# S03.net
KiCad netlist of a schematic drawn in Altium Designer
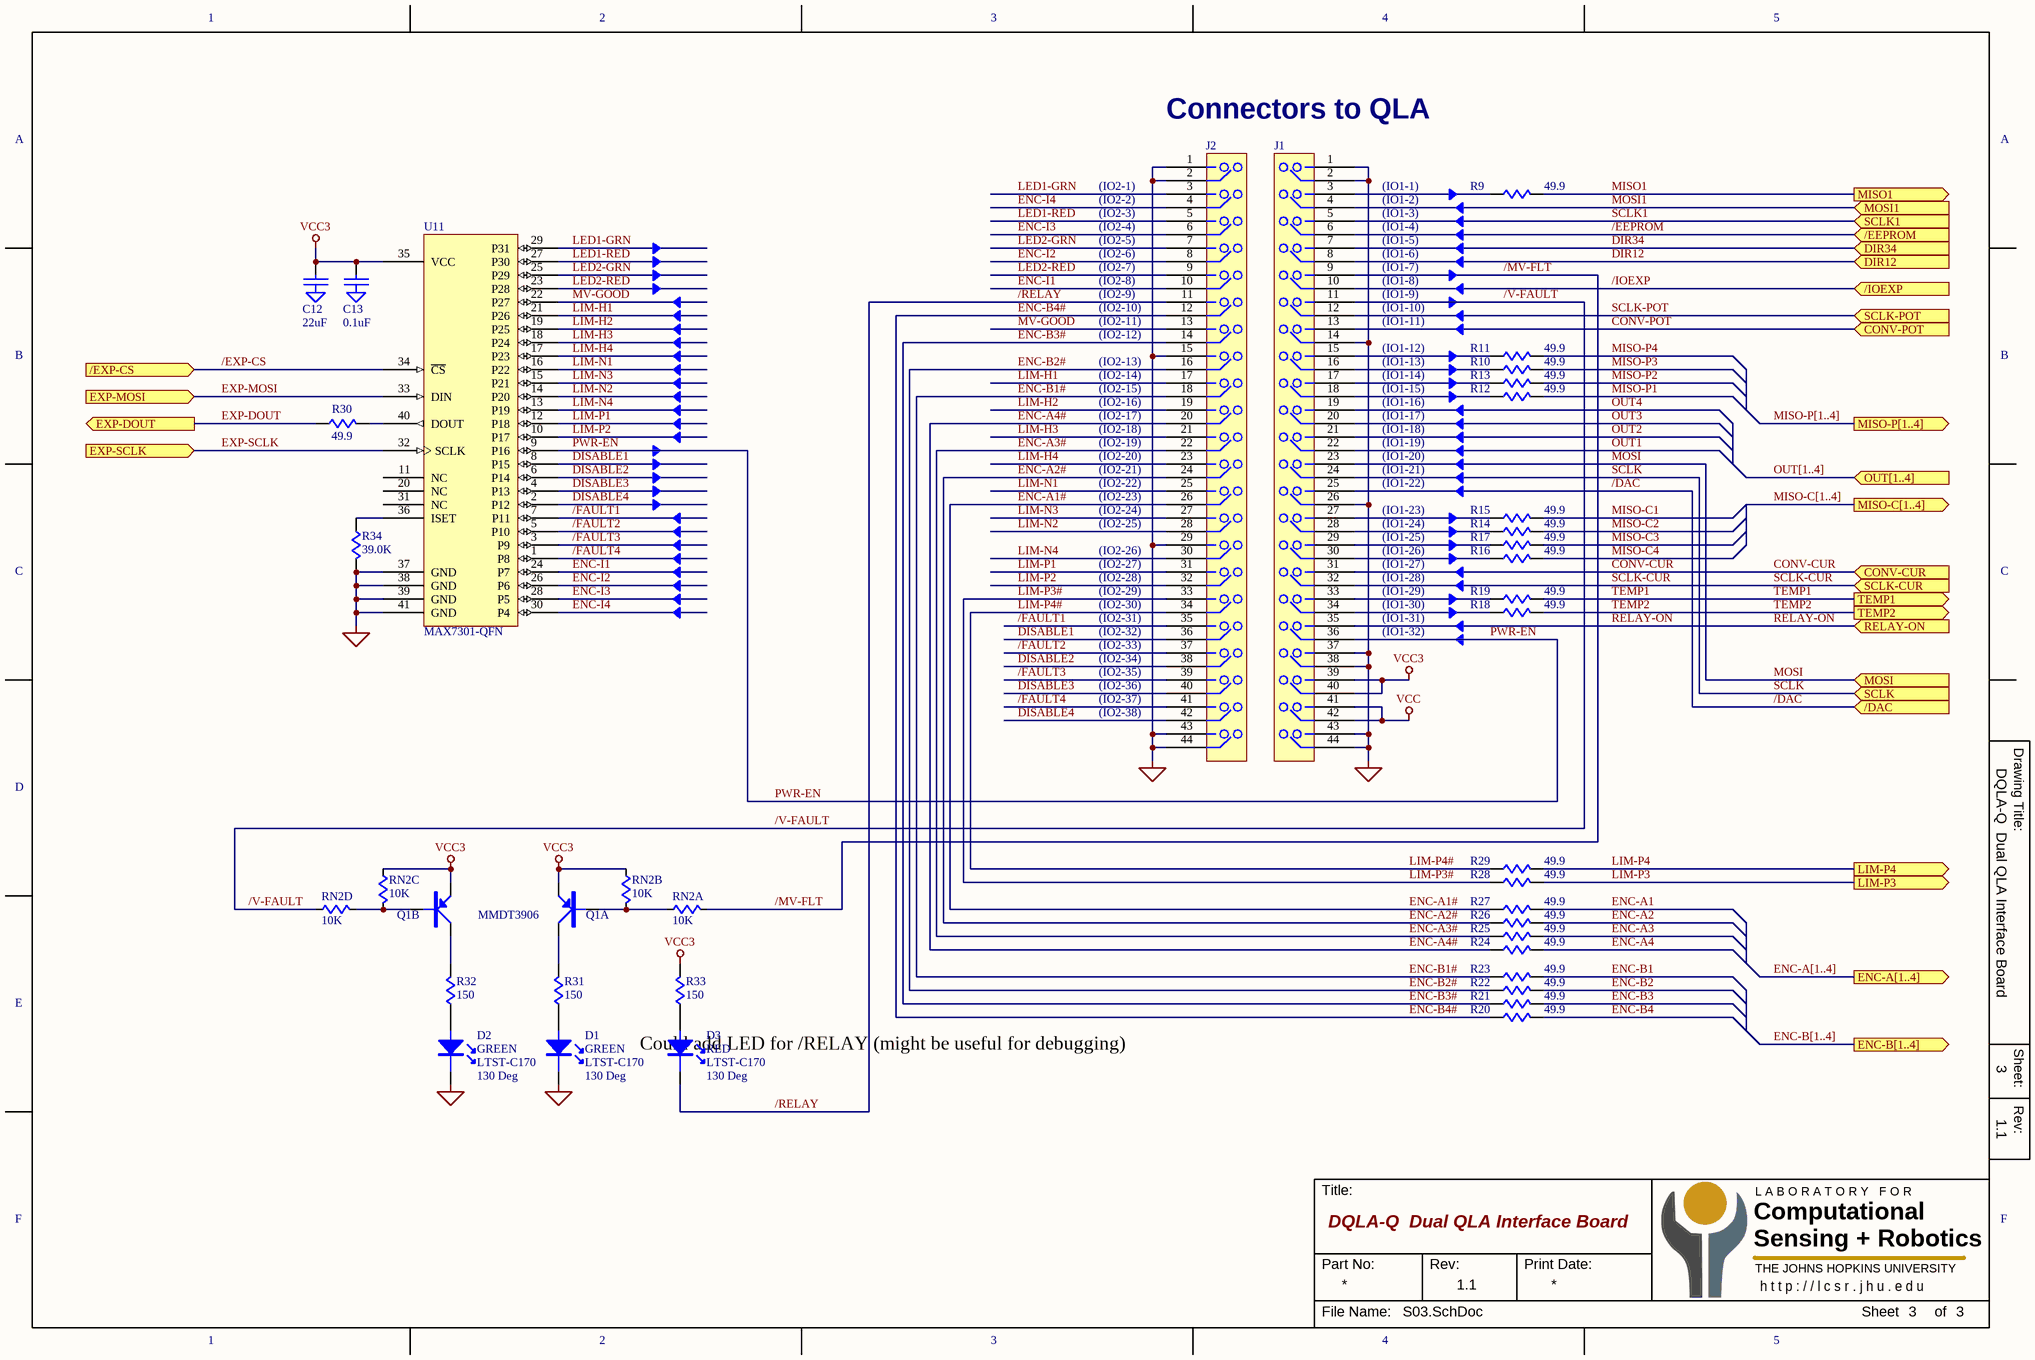
[diagram p0: S03.SchDoc]

(export (version "E")
  (design (tool "Eeschema 10.0.6"))
  (components
    (comp (ref "C12") (value "22uF") (footprint "C0805") (libsource (lib "LibJHU") (part "CAP-GND")))
    (comp (ref "C13") (value "0.1uF") (footprint "C0402") (libsource (lib "LibJHU") (part "CAP-GND")))
    (comp (ref "D1")
      (value "LED")
      (footprint "LED-0805")
      (fields
        (field (name "COLOR") "GREEN")
        (field (name "P/N") "LTST-C170")
        (field (name "ANGLE") "130 Deg")
      )
      (libsource (lib "LibJHU") (part "LED"))
    )
    (comp (ref "D2")
      (value "LED")
      (footprint "LED-0805")
      (fields
        (field (name "COLOR") "GREEN")
        (field (name "P/N") "LTST-C170")
        (field (name "ANGLE") "130 Deg")
      )
      (libsource (lib "LibJHU") (part "LED"))
    )
    (comp (ref "D3")
      (value "LED")
      (footprint "LED-0805")
      (fields (field (name "COLOR") "RED") (field (name "P/N") "LTST-C170") (field (name "ANGLE") "130 Deg"))
      (libsource (lib "LibJHU") (part "LED"))
    )
    (comp (ref "J1")
      (value "HEADER 22x2-1")
      (footprint "HDR-22x2-2MM")
      (libsource (lib "LibJHU") (part "HEADER 22x2-1"))
    )
    (comp (ref "J2")
      (value "HEADER 22x2-1")
      (footprint "HDR-22x2-2MM")
      (libsource (lib "LibJHU") (part "HEADER 22x2-1"))
    )
    (comp (ref "Q1")
      (value "MMDT3906")
      (footprint "SC70-6-NP")
      (libsource (lib "LibJHU") (part "PNP-DUAL-DIAG"))
    )
    (comp (ref "R9") (value "49.9") (footprint "R0402") (libsource (lib "LibJHU") (part "R")))
    (comp (ref "R10") (value "49.9") (footprint "R0402") (libsource (lib "LibJHU") (part "R")))
    (comp (ref "R11") (value "49.9") (footprint "R0402") (libsource (lib "LibJHU") (part "R")))
    (comp (ref "R12") (value "49.9") (footprint "R0402") (libsource (lib "LibJHU") (part "R")))
    (comp (ref "R13") (value "49.9") (footprint "R0402") (libsource (lib "LibJHU") (part "R")))
    (comp (ref "R14") (value "49.9") (footprint "R0402") (libsource (lib "LibJHU") (part "R")))
    (comp (ref "R15") (value "49.9") (footprint "R0402") (libsource (lib "LibJHU") (part "R")))
    (comp (ref "R16") (value "49.9") (footprint "R0402") (libsource (lib "LibJHU") (part "R")))
    (comp (ref "R17") (value "49.9") (footprint "R0402") (libsource (lib "LibJHU") (part "R")))
    (comp (ref "R18") (value "49.9") (footprint "R0402") (libsource (lib "LibJHU") (part "R")))
    (comp (ref "R19") (value "49.9") (footprint "R0402") (libsource (lib "LibJHU") (part "R")))
    (comp (ref "R20") (value "49.9") (footprint "R0402") (libsource (lib "LibJHU") (part "R")))
    (comp (ref "R21") (value "49.9") (footprint "R0402") (libsource (lib "LibJHU") (part "R")))
    (comp (ref "R22") (value "49.9") (footprint "R0402") (libsource (lib "LibJHU") (part "R")))
    (comp (ref "R23") (value "49.9") (footprint "R0402") (libsource (lib "LibJHU") (part "R")))
    (comp (ref "R24") (value "49.9") (footprint "R0402") (libsource (lib "LibJHU") (part "R")))
    (comp (ref "R25") (value "49.9") (footprint "R0402") (libsource (lib "LibJHU") (part "R")))
    (comp (ref "R26") (value "49.9") (footprint "R0402") (libsource (lib "LibJHU") (part "R")))
    (comp (ref "R27") (value "49.9") (footprint "R0402") (libsource (lib "LibJHU") (part "R")))
    (comp (ref "R28") (value "49.9") (footprint "R0402") (libsource (lib "LibJHU") (part "R")))
    (comp (ref "R29") (value "49.9") (footprint "R0402") (libsource (lib "LibJHU") (part "R")))
    (comp (ref "R30") (value "49.9") (footprint "R0402") (libsource (lib "LibJHU") (part "R")))
    (comp (ref "R31") (value "150") (footprint "R0603") (libsource (lib "LibJHU") (part "R")))
    (comp (ref "R32") (value "150") (footprint "R0603") (libsource (lib "LibJHU") (part "R")))
    (comp (ref "R33") (value "150") (footprint "R0603") (libsource (lib "LibJHU") (part "R")))
    (comp (ref "R34") (value "39.0K") (footprint "R0402") (libsource (lib "") (part "R_1")))
    (comp (ref "RN2")
      (value "10K")
      (footprint "RN-742C083")
      (libsource (lib "LibJHU") (part "RN-DISC-SM-4X"))
    )
    (comp (ref "U11")
      (value "MAX7301-QFN")
      (footprint "QFN-40-6mm")
      (libsource (lib "LibJHU") (part "MAX7301-QFN"))
    )
  )
  (nets
    (net (code "1") (name "/CONV-CUR") (class "Default")
      (node (ref "J1") (pin "31") (pinfunction "31_31") (pintype "passive"))
    )
    (net (code "2") (name "/CONV-POT") (class "Default")
      (node (ref "J1") (pin "13") (pinfunction "13_13") (pintype "passive"))
    )
    (net (code "3") (name "/DIR12") (class "Default")
      (node (ref "J1") (pin "8") (pinfunction "8_8") (pintype "passive"))
    )
    (net (code "4") (name "/DIR34") (class "Default")
      (node (ref "J1") (pin "7") (pinfunction "7_7") (pintype "passive"))
    )
    (net (code "5") (name "/DISABLE1") (class "Default")
      (node (ref "J2") (pin "36") (pinfunction "36_36") (pintype "passive"))
      (node (ref "U11") (pin "8") (pinfunction "P15_8") (pintype "bidirectional"))
    )
    (net (code "6") (name "/DISABLE2") (class "Default")
      (node (ref "J2") (pin "38") (pinfunction "38_38") (pintype "passive"))
      (node (ref "U11") (pin "6") (pinfunction "P14_6") (pintype "bidirectional"))
    )
    (net (code "7") (name "/DISABLE3") (class "Default")
      (node (ref "J2") (pin "40") (pinfunction "40_40") (pintype "passive"))
      (node (ref "U11") (pin "4") (pinfunction "P13_4") (pintype "bidirectional"))
    )
    (net (code "8") (name "/DISABLE4") (class "Default")
      (node (ref "J2") (pin "42") (pinfunction "42_42") (pintype "passive"))
      (node (ref "U11") (pin "2") (pinfunction "P12_2") (pintype "bidirectional"))
    )
    (net (code "9") (name "/ENC-A1") (class "Default")
      (node (ref "R27") (pin "2") (pinfunction "2_2") (pintype "passive"))
    )
    (net (code "10") (name "/ENC-A1#") (class "Default")
      (node (ref "J2") (pin "26") (pinfunction "26_26") (pintype "passive"))
      (node (ref "R27") (pin "1") (pinfunction "1_1") (pintype "passive"))
    )
    (net (code "11") (name "/ENC-A2") (class "Default")
      (node (ref "R26") (pin "2") (pinfunction "2_2") (pintype "passive"))
    )
    (net (code "12") (name "/ENC-A2#") (class "Default")
      (node (ref "J2") (pin "24") (pinfunction "24_24") (pintype "passive"))
      (node (ref "R26") (pin "1") (pinfunction "1_1") (pintype "passive"))
    )
    (net (code "13") (name "/ENC-A3") (class "Default")
      (node (ref "R25") (pin "2") (pinfunction "2_2") (pintype "passive"))
    )
    (net (code "14") (name "/ENC-A3#") (class "Default")
      (node (ref "J2") (pin "22") (pinfunction "22_22") (pintype "passive"))
      (node (ref "R25") (pin "1") (pinfunction "1_1") (pintype "passive"))
    )
    (net (code "15") (name "/ENC-A4") (class "Default")
      (node (ref "R24") (pin "2") (pinfunction "2_2") (pintype "passive"))
    )
    (net (code "16") (name "/ENC-A4#") (class "Default")
      (node (ref "J2") (pin "20") (pinfunction "20_20") (pintype "passive"))
      (node (ref "R24") (pin "1") (pinfunction "1_1") (pintype "passive"))
    )
    (net (code "18") (name "/ENC-B1") (class "Default")
      (node (ref "R23") (pin "2") (pinfunction "2_2") (pintype "passive"))
    )
    (net (code "19") (name "/ENC-B1#") (class "Default")
      (node (ref "J2") (pin "18") (pinfunction "18_18") (pintype "passive"))
      (node (ref "R23") (pin "1") (pinfunction "1_1") (pintype "passive"))
    )
    (net (code "20") (name "/ENC-B2") (class "Default")
      (node (ref "R22") (pin "2") (pinfunction "2_2") (pintype "passive"))
    )
    (net (code "21") (name "/ENC-B2#") (class "Default")
      (node (ref "J2") (pin "16") (pinfunction "16_16") (pintype "passive"))
      (node (ref "R22") (pin "1") (pinfunction "1_1") (pintype "passive"))
    )
    (net (code "22") (name "/ENC-B3") (class "Default")
      (node (ref "R21") (pin "2") (pinfunction "2_2") (pintype "passive"))
    )
    (net (code "23") (name "/ENC-B3#") (class "Default")
      (node (ref "J2") (pin "14") (pinfunction "14_14") (pintype "passive"))
      (node (ref "R21") (pin "1") (pinfunction "1_1") (pintype "passive"))
    )
    (net (code "24") (name "/ENC-B4") (class "Default")
      (node (ref "R20") (pin "2") (pinfunction "2_2") (pintype "passive"))
    )
    (net (code "25") (name "/ENC-B4#") (class "Default")
      (node (ref "J2") (pin "12") (pinfunction "12_12") (pintype "passive"))
      (node (ref "R20") (pin "1") (pinfunction "1_1") (pintype "passive"))
    )
    (net (code "27") (name "/ENC-I1") (class "Default")
      (node (ref "J2") (pin "10") (pinfunction "10_10") (pintype "passive"))
      (node (ref "U11") (pin "24") (pinfunction "P7_24") (pintype "bidirectional"))
    )
    (net (code "28") (name "/ENC-I2") (class "Default")
      (node (ref "J2") (pin "8") (pinfunction "8_8") (pintype "passive"))
      (node (ref "U11") (pin "26") (pinfunction "P6_26") (pintype "bidirectional"))
    )
    (net (code "29") (name "/ENC-I3") (class "Default")
      (node (ref "J2") (pin "6") (pinfunction "6_6") (pintype "passive"))
      (node (ref "U11") (pin "28") (pinfunction "P5_28") (pintype "bidirectional"))
    )
    (net (code "30") (name "/ENC-I4") (class "Default")
      (node (ref "J2") (pin "4") (pinfunction "4_4") (pintype "passive"))
      (node (ref "U11") (pin "30") (pinfunction "P4_30") (pintype "bidirectional"))
    )
    (net (code "31") (name "/EXP-DOUT") (class "Default")
      (node (ref "R30") (pin "1") (pinfunction "1_1") (pintype "passive"))
    )
    (net (code "32") (name "/EXP-MOSI") (class "Default")
      (node (ref "U11") (pin "33") (pinfunction "DIN_33") (pintype "input"))
    )
    (net (code "33") (name "/EXP-SCLK") (class "Default")
      (node (ref "U11") (pin "32") (pinfunction "SCLK_32") (pintype "input"))
    )
    (net (code "34") (name "/LED1-GRN") (class "Default")
      (node (ref "J2") (pin "3") (pinfunction "3_3") (pintype "passive"))
      (node (ref "U11") (pin "29") (pinfunction "P31_29") (pintype "bidirectional"))
    )
    (net (code "35") (name "/LED1-RED") (class "Default")
      (node (ref "J2") (pin "5") (pinfunction "5_5") (pintype "passive"))
      (node (ref "U11") (pin "27") (pinfunction "P30_27") (pintype "bidirectional"))
    )
    (net (code "36") (name "/LED2-GRN") (class "Default")
      (node (ref "J2") (pin "7") (pinfunction "7_7") (pintype "passive"))
      (node (ref "U11") (pin "25") (pinfunction "P29_25") (pintype "bidirectional"))
    )
    (net (code "37") (name "/LED2-RED") (class "Default")
      (node (ref "J2") (pin "9") (pinfunction "9_9") (pintype "passive"))
      (node (ref "U11") (pin "23") (pinfunction "P28_23") (pintype "bidirectional"))
    )
    (net (code "38") (name "/LIM-H1") (class "Default")
      (node (ref "J2") (pin "17") (pinfunction "17_17") (pintype "passive"))
      (node (ref "U11") (pin "21") (pinfunction "P26_21") (pintype "bidirectional"))
    )
    (net (code "39") (name "/LIM-H2") (class "Default")
      (node (ref "J2") (pin "19") (pinfunction "19_19") (pintype "passive"))
      (node (ref "U11") (pin "19") (pinfunction "P25_19") (pintype "bidirectional"))
    )
    (net (code "40") (name "/LIM-H3") (class "Default")
      (node (ref "J2") (pin "21") (pinfunction "21_21") (pintype "passive"))
      (node (ref "U11") (pin "18") (pinfunction "P24_18") (pintype "bidirectional"))
    )
    (net (code "41") (name "/LIM-H4") (class "Default")
      (node (ref "J2") (pin "23") (pinfunction "23_23") (pintype "passive"))
      (node (ref "U11") (pin "17") (pinfunction "P23_17") (pintype "bidirectional"))
    )
    (net (code "42") (name "/LIM-N1") (class "Default")
      (node (ref "J2") (pin "25") (pinfunction "25_25") (pintype "passive"))
      (node (ref "U11") (pin "16") (pinfunction "P22_16") (pintype "bidirectional"))
    )
    (net (code "43") (name "/LIM-N2") (class "Default")
      (node (ref "J2") (pin "28") (pinfunction "28_28") (pintype "passive"))
      (node (ref "U11") (pin "14") (pinfunction "P20_14") (pintype "bidirectional"))
    )
    (net (code "44") (name "/LIM-N3") (class "Default")
      (node (ref "J2") (pin "27") (pinfunction "27_27") (pintype "passive"))
      (node (ref "U11") (pin "15") (pinfunction "P21_15") (pintype "bidirectional"))
    )
    (net (code "45") (name "/LIM-N4") (class "Default")
      (node (ref "J2") (pin "30") (pinfunction "30_30") (pintype "passive"))
      (node (ref "U11") (pin "13") (pinfunction "P19_13") (pintype "bidirectional"))
    )
    (net (code "46") (name "/LIM-P1") (class "Default")
      (node (ref "J2") (pin "31") (pinfunction "31_31") (pintype "passive"))
      (node (ref "U11") (pin "12") (pinfunction "P18_12") (pintype "bidirectional"))
    )
    (net (code "47") (name "/LIM-P2") (class "Default")
      (node (ref "J2") (pin "32") (pinfunction "32_32") (pintype "passive"))
      (node (ref "U11") (pin "10") (pinfunction "P17_10") (pintype "bidirectional"))
    )
    (net (code "48") (name "/LIM-P3") (class "Default")
      (node (ref "R28") (pin "2") (pinfunction "2_2") (pintype "passive"))
    )
    (net (code "49") (name "/LIM-P3#") (class "Default")
      (node (ref "J2") (pin "33") (pinfunction "33_33") (pintype "passive"))
      (node (ref "R28") (pin "1") (pinfunction "1_1") (pintype "passive"))
    )
    (net (code "50") (name "/LIM-P4") (class "Default")
      (node (ref "R29") (pin "2") (pinfunction "2_2") (pintype "passive"))
    )
    (net (code "51") (name "/LIM-P4#") (class "Default")
      (node (ref "J2") (pin "34") (pinfunction "34_34") (pintype "passive"))
      (node (ref "R29") (pin "1") (pinfunction "1_1") (pintype "passive"))
    )
    (net (code "52") (name "/MISO-C1") (class "Default")
      (node (ref "R15") (pin "2") (pinfunction "2_2") (pintype "passive"))
    )
    (net (code "53") (name "/MISO-C2") (class "Default")
      (node (ref "R14") (pin "2") (pinfunction "2_2") (pintype "passive"))
    )
    (net (code "54") (name "/MISO-C3") (class "Default")
      (node (ref "R17") (pin "2") (pinfunction "2_2") (pintype "passive"))
    )
    (net (code "55") (name "/MISO-C4") (class "Default")
      (node (ref "R16") (pin "2") (pinfunction "2_2") (pintype "passive"))
    )
    (net (code "57") (name "/MISO-P1") (class "Default")
      (node (ref "R12") (pin "2") (pinfunction "2_2") (pintype "passive"))
    )
    (net (code "58") (name "/MISO-P2") (class "Default")
      (node (ref "R13") (pin "2") (pinfunction "2_2") (pintype "passive"))
    )
    (net (code "59") (name "/MISO-P3") (class "Default")
      (node (ref "R10") (pin "2") (pinfunction "2_2") (pintype "passive"))
    )
    (net (code "60") (name "/MISO-P4") (class "Default")
      (node (ref "R11") (pin "2") (pinfunction "2_2") (pintype "passive"))
    )
    (net (code "62") (name "/MISO1") (class "Default")
      (node (ref "R9") (pin "2") (pinfunction "2_2") (pintype "passive"))
    )
    (net (code "63") (name "/MOSI") (class "Default")
      (node (ref "J1") (pin "23") (pinfunction "23_23") (pintype "passive"))
    )
    (net (code "64") (name "/MOSI1") (class "Default")
      (node (ref "J1") (pin "4") (pinfunction "4_4") (pintype "passive"))
    )
    (net (code "65") (name "/MV-GOOD") (class "Default")
      (node (ref "J2") (pin "13") (pinfunction "13_13") (pintype "passive"))
      (node (ref "U11") (pin "22") (pinfunction "P27_22") (pintype "bidirectional"))
    )
    (net (code "66") (name "/OUT1") (class "Default")
      (node (ref "J1") (pin "22") (pinfunction "22_22") (pintype "passive"))
    )
    (net (code "67") (name "/OUT2") (class "Default")
      (node (ref "J1") (pin "21") (pinfunction "21_21") (pintype "passive"))
    )
    (net (code "68") (name "/OUT3") (class "Default")
      (node (ref "J1") (pin "20") (pinfunction "20_20") (pintype "passive"))
    )
    (net (code "69") (name "/OUT4") (class "Default")
      (node (ref "J1") (pin "19") (pinfunction "19_19") (pintype "passive"))
    )
    (net (code "71") (name "/PWR-EN") (class "Default")
      (node (ref "J1") (pin "36") (pinfunction "36_36") (pintype "passive"))
      (node (ref "U11") (pin "9") (pinfunction "P16_9") (pintype "bidirectional"))
    )
    (net (code "72") (name "/RELAY-ON") (class "Default")
      (node (ref "J1") (pin "35") (pinfunction "35_35") (pintype "passive"))
    )
    (net (code "73") (name "/SCLK") (class "Default")
      (node (ref "J1") (pin "24") (pinfunction "24_24") (pintype "passive"))
    )
    (net (code "74") (name "/SCLK-CUR") (class "Default")
      (node (ref "J1") (pin "32") (pinfunction "32_32") (pintype "passive"))
    )
    (net (code "75") (name "/SCLK-POT") (class "Default")
      (node (ref "J1") (pin "12") (pinfunction "12_12") (pintype "passive"))
    )
    (net (code "76") (name "/SCLK1") (class "Default")
      (node (ref "J1") (pin "5") (pinfunction "5_5") (pintype "passive"))
    )
    (net (code "77") (name "/TEMP1") (class "Default")
      (node (ref "R19") (pin "2") (pinfunction "2_2") (pintype "passive"))
    )
    (net (code "78") (name "/TEMP2") (class "Default")
      (node (ref "R18") (pin "2") (pinfunction "2_2") (pintype "passive"))
    )
    (net (code "79") (name "/{slash}DAC") (class "Default")
      (node (ref "J1") (pin "25") (pinfunction "25_25") (pintype "passive"))
    )
    (net (code "80") (name "/{slash}EEPROM") (class "Default")
      (node (ref "J1") (pin "6") (pinfunction "6_6") (pintype "passive"))
    )
    (net (code "81") (name "/{slash}EXP-CS") (class "Default")
      (node (ref "U11") (pin "34") (pinfunction "CS_34") (pintype "input"))
    )
    (net (code "82") (name "/{slash}FAULT1") (class "Default")
      (node (ref "J2") (pin "35") (pinfunction "35_35") (pintype "passive"))
      (node (ref "U11") (pin "7") (pinfunction "P11_7") (pintype "bidirectional"))
    )
    (net (code "83") (name "/{slash}FAULT2") (class "Default")
      (node (ref "J2") (pin "37") (pinfunction "37_37") (pintype "passive"))
      (node (ref "U11") (pin "5") (pinfunction "P10_5") (pintype "bidirectional"))
    )
    (net (code "84") (name "/{slash}FAULT3") (class "Default")
      (node (ref "J2") (pin "39") (pinfunction "39_39") (pintype "passive"))
      (node (ref "U11") (pin "3") (pinfunction "P9_3") (pintype "bidirectional"))
    )
    (net (code "85") (name "/{slash}FAULT4") (class "Default")
      (node (ref "J2") (pin "41") (pinfunction "41_41") (pintype "passive"))
      (node (ref "U11") (pin "1") (pinfunction "P8_1") (pintype "bidirectional"))
    )
    (net (code "86") (name "/{slash}IOEXP") (class "Default")
      (node (ref "J1") (pin "10") (pinfunction "10_10") (pintype "passive"))
    )
    (net (code "87") (name "/{slash}MV-FLT") (class "Default")
      (node (ref "J1") (pin "9") (pinfunction "9_9") (pintype "passive"))
      (node (ref "RN2") (pin "1") (pinfunction "1_1") (pintype "passive"))
    )
    (net (code "88") (name "/{slash}RELAY") (class "Default")
      (node (ref "D3") (pin "1") (pinfunction "C_1") (pintype "passive"))
      (node (ref "J2") (pin "11") (pinfunction "11_11") (pintype "passive"))
    )
    (net (code "89") (name "/{slash}V-FAULT") (class "Default")
      (node (ref "J1") (pin "11") (pinfunction "11_11") (pintype "passive"))
      (node (ref "RN2") (pin "4") (pinfunction "4_4") (pintype "passive"))
    )
    (net (code "90") (name "GND") (class "Default")
      (node (ref "C12") (pin "2") (pinfunction "GND_2") (pintype "power_in"))
      (node (ref "C13") (pin "2") (pinfunction "GND_2") (pintype "power_in"))
      (node (ref "D1") (pin "1") (pinfunction "C_1") (pintype "passive"))
      (node (ref "D2") (pin "1") (pinfunction "C_1") (pintype "passive"))
      (node (ref "J1") (pin "1") (pinfunction "1_1") (pintype "passive"))
      (node (ref "J1") (pin "14") (pinfunction "14_14") (pintype "passive"))
      (node (ref "J1") (pin "2") (pinfunction "2_2") (pintype "passive"))
      (node (ref "J1") (pin "26") (pinfunction "26_26") (pintype "passive"))
      (node (ref "J1") (pin "37") (pinfunction "37_37") (pintype "passive"))
      (node (ref "J1") (pin "38") (pinfunction "38_38") (pintype "passive"))
      (node (ref "J1") (pin "43") (pinfunction "43_43") (pintype "passive"))
      (node (ref "J1") (pin "44") (pinfunction "44_44") (pintype "passive"))
      (node (ref "J2") (pin "1") (pinfunction "1_1") (pintype "passive"))
      (node (ref "J2") (pin "15") (pinfunction "15_15") (pintype "passive"))
      (node (ref "J2") (pin "2") (pinfunction "2_2") (pintype "passive"))
      (node (ref "J2") (pin "29") (pinfunction "29_29") (pintype "passive"))
      (node (ref "J2") (pin "43") (pinfunction "43_43") (pintype "passive"))
      (node (ref "J2") (pin "44") (pinfunction "44_44") (pintype "passive"))
      (node (ref "R34") (pin "2") (pinfunction "2_2") (pintype "passive"))
      (node (ref "U11") (pin "37") (pinfunction "GND_37") (pintype "power_in"))
      (node (ref "U11") (pin "38") (pinfunction "GND_38") (pintype "power_in"))
      (node (ref "U11") (pin "39") (pinfunction "GND_39") (pintype "power_in"))
      (node (ref "U11") (pin "41") (pinfunction "GND_41") (pintype "power_in"))
    )
    (net (code "91") (name "Net-(D1-A)") (class "Default")
      (node (ref "D1") (pin "2") (pinfunction "A_2") (pintype "passive"))
      (node (ref "R31") (pin "1") (pinfunction "1_1") (pintype "passive"))
    )
    (net (code "92") (name "Net-(D2-A)") (class "Default")
      (node (ref "D2") (pin "2") (pinfunction "A_2") (pintype "passive"))
      (node (ref "R32") (pin "1") (pinfunction "1_1") (pintype "passive"))
    )
    (net (code "93") (name "Net-(D3-A)") (class "Default")
      (node (ref "D3") (pin "2") (pinfunction "A_2") (pintype "passive"))
      (node (ref "R33") (pin "1") (pinfunction "1_1") (pintype "passive"))
    )
    (net (code "94") (name "Net-(J1-Pad3)") (class "Default")
      (node (ref "J1") (pin "3") (pinfunction "3_3") (pintype "passive"))
      (node (ref "R9") (pin "1") (pinfunction "1_1") (pintype "passive"))
    )
    (net (code "95") (name "Net-(J1-Pad15)") (class "Default")
      (node (ref "J1") (pin "15") (pinfunction "15_15") (pintype "passive"))
      (node (ref "R11") (pin "1") (pinfunction "1_1") (pintype "passive"))
    )
    (net (code "96") (name "Net-(J1-Pad16)") (class "Default")
      (node (ref "J1") (pin "16") (pinfunction "16_16") (pintype "passive"))
      (node (ref "R10") (pin "1") (pinfunction "1_1") (pintype "passive"))
    )
    (net (code "97") (name "Net-(J1-Pad17)") (class "Default")
      (node (ref "J1") (pin "17") (pinfunction "17_17") (pintype "passive"))
      (node (ref "R13") (pin "1") (pinfunction "1_1") (pintype "passive"))
    )
    (net (code "98") (name "Net-(J1-Pad18)") (class "Default")
      (node (ref "J1") (pin "18") (pinfunction "18_18") (pintype "passive"))
      (node (ref "R12") (pin "1") (pinfunction "1_1") (pintype "passive"))
    )
    (net (code "99") (name "Net-(J1-Pad27)") (class "Default")
      (node (ref "J1") (pin "27") (pinfunction "27_27") (pintype "passive"))
      (node (ref "R15") (pin "1") (pinfunction "1_1") (pintype "passive"))
    )
    (net (code "100") (name "Net-(J1-Pad28)") (class "Default")
      (node (ref "J1") (pin "28") (pinfunction "28_28") (pintype "passive"))
      (node (ref "R14") (pin "1") (pinfunction "1_1") (pintype "passive"))
    )
    (net (code "101") (name "Net-(J1-Pad29)") (class "Default")
      (node (ref "J1") (pin "29") (pinfunction "29_29") (pintype "passive"))
      (node (ref "R17") (pin "1") (pinfunction "1_1") (pintype "passive"))
    )
    (net (code "102") (name "Net-(J1-Pad30)") (class "Default")
      (node (ref "J1") (pin "30") (pinfunction "30_30") (pintype "passive"))
      (node (ref "R16") (pin "1") (pinfunction "1_1") (pintype "passive"))
    )
    (net (code "103") (name "Net-(J1-Pad33)") (class "Default")
      (node (ref "J1") (pin "33") (pinfunction "33_33") (pintype "passive"))
      (node (ref "R19") (pin "1") (pinfunction "1_1") (pintype "passive"))
    )
    (net (code "104") (name "Net-(J1-Pad34)") (class "Default")
      (node (ref "J1") (pin "34") (pinfunction "34_34") (pintype "passive"))
      (node (ref "R18") (pin "1") (pinfunction "1_1") (pintype "passive"))
    )
    (net (code "105") (name "Net-(Q1A-B)") (class "Default")
      (node (ref "Q1") (pin "2") (pinfunction "B_2") (pintype "passive"))
      (node (ref "RN2") (pin "7") (pinfunction "7_7") (pintype "passive"))
      (node (ref "RN2") (pin "8") (pinfunction "8_8") (pintype "passive"))
    )
    (net (code "106") (name "Net-(Q1A-C)") (class "Default")
      (node (ref "Q1") (pin "6") (pinfunction "C_6") (pintype "passive"))
      (node (ref "R31") (pin "2") (pinfunction "2_2") (pintype "passive"))
    )
    (net (code "107") (name "Net-(Q1B-B)") (class "Default")
      (node (ref "Q1") (pin "5") (pinfunction "B_5") (pintype "passive"))
      (node (ref "RN2") (pin "5") (pinfunction "5_5") (pintype "passive"))
      (node (ref "RN2") (pin "6") (pinfunction "6_6") (pintype "passive"))
    )
    (net (code "108") (name "Net-(Q1B-C)") (class "Default")
      (node (ref "Q1") (pin "3") (pinfunction "C_3") (pintype "passive"))
      (node (ref "R32") (pin "2") (pinfunction "2_2") (pintype "passive"))
    )
    (net (code "109") (name "Net-(U11-DOUT)") (class "Default")
      (node (ref "R30") (pin "2") (pinfunction "2_2") (pintype "passive"))
      (node (ref "U11") (pin "40") (pinfunction "DOUT_40") (pintype "output"))
    )
    (net (code "110") (name "Net-(U11-ISET)") (class "Default")
      (node (ref "R34") (pin "1") (pinfunction "1_1") (pintype "passive"))
      (node (ref "U11") (pin "36") (pinfunction "ISET_36") (pintype "passive"))
    )
    (net (code "111") (name "VCC") (class "Default")
      (node (ref "J1") (pin "41") (pinfunction "41_41") (pintype "passive"))
      (node (ref "J1") (pin "42") (pinfunction "42_42") (pintype "passive"))
    )
    (net (code "112") (name "VCC3") (class "Default")
      (node (ref "C12") (pin "1") (pintype "passive"))
      (node (ref "C13") (pin "1") (pintype "passive"))
      (node (ref "J1") (pin "39") (pinfunction "39_39") (pintype "passive"))
      (node (ref "J1") (pin "40") (pinfunction "40_40") (pintype "passive"))
      (node (ref "Q1") (pin "1") (pinfunction "E_1") (pintype "passive"))
      (node (ref "Q1") (pin "4") (pinfunction "E_4") (pintype "passive"))
      (node (ref "R33") (pin "2") (pinfunction "2_2") (pintype "passive"))
      (node (ref "RN2") (pin "2") (pinfunction "2_2") (pintype "passive"))
      (node (ref "RN2") (pin "3") (pinfunction "3_3") (pintype "passive"))
      (node (ref "U11") (pin "35") (pinfunction "VCC_35") (pintype "power_in"))
    )
    (net (code "113") (name "unconnected-(U11-NC-Pad11)") (class "Default")
      (node (ref "U11") (pin "11") (pinfunction "NC_11") (pintype "passive"))
    )
    (net (code "114") (name "unconnected-(U11-NC-Pad20)") (class "Default")
      (node (ref "U11") (pin "20") (pinfunction "NC_20") (pintype "passive"))
    )
    (net (code "115") (name "unconnected-(U11-NC-Pad31)") (class "Default")
      (node (ref "U11") (pin "31") (pinfunction "NC_31") (pintype "passive"))
    )
  )
)
